# LTX-Rapidfire.net
KiCad netlist of a schematic drawn in EAGLE
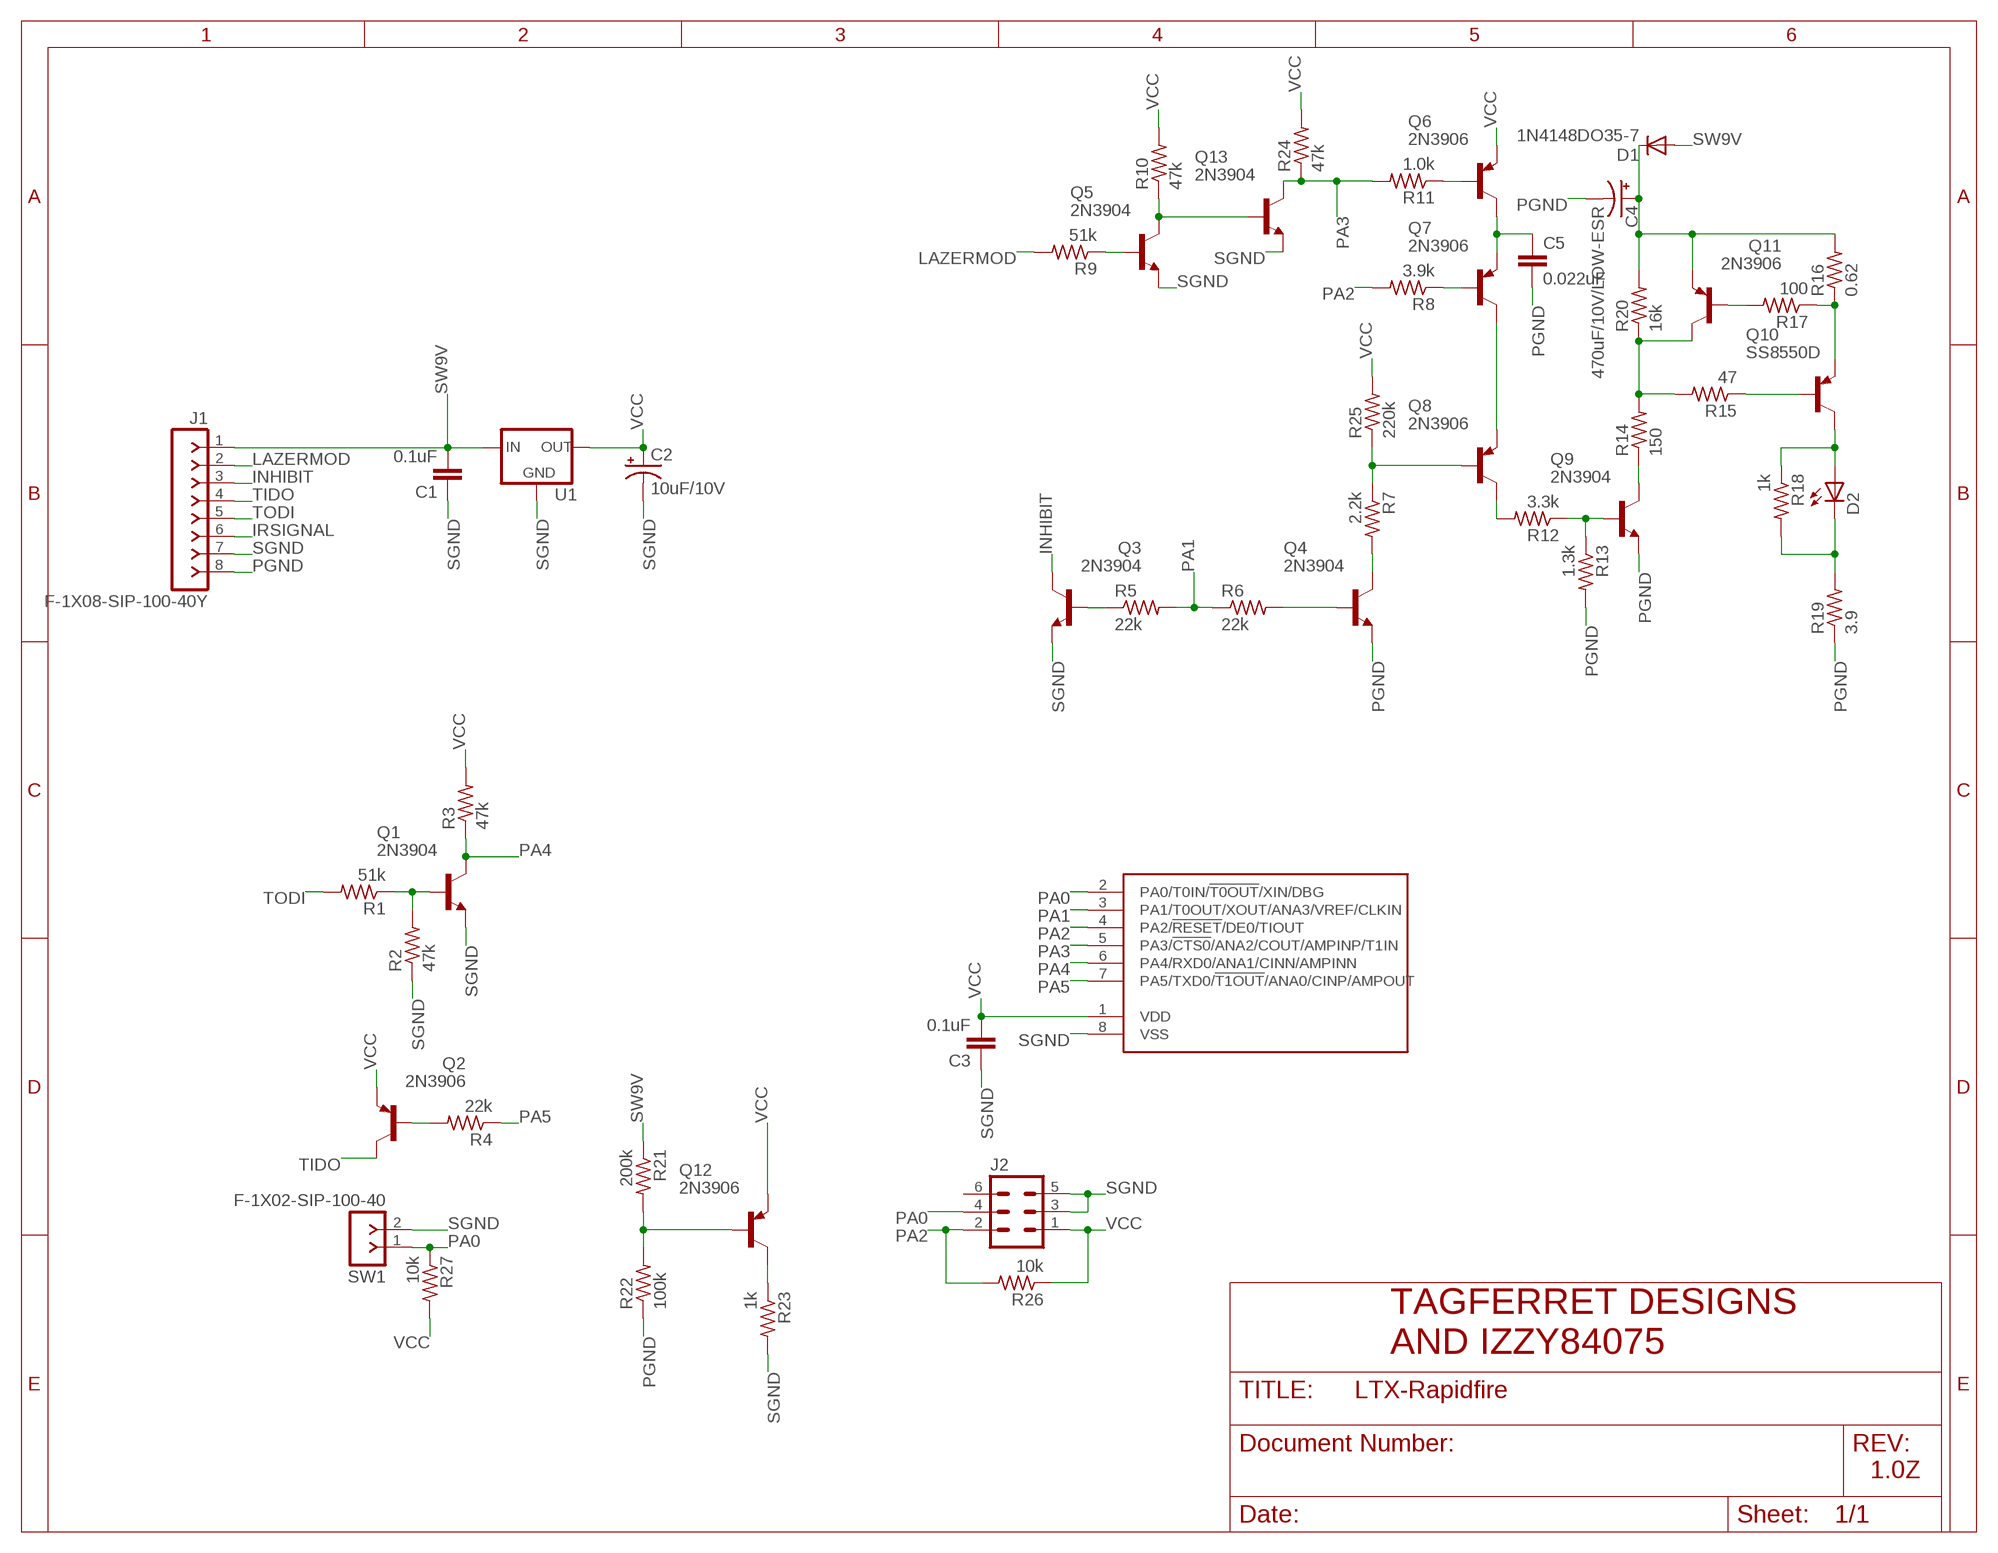
[diagram p0: schematic, sheet 1]

(export (version "E")
  (design (tool "Eeschema 10.0.6"))
  (components
    (comp (ref "C1")
      (value "0.1uF")
      (footprint "eagle-import:C025-025X050")
      (libsource (lib "eagle-import") (part "C-EU025-025X050"))
    )
    (comp (ref "C2")
      (value "10uF/10V")
      (footprint "eagle-import:E2-4")
      (libsource (lib "eagle-import") (part "CPOL-USE2-4"))
    )
    (comp (ref "C3")
      (value "0.1uF")
      (footprint "eagle-import:C025-025X050")
      (libsource (lib "eagle-import") (part "C-EU025-025X050"))
    )
    (comp (ref "C4")
      (value "470uF/10V/LOW-ESR")
      (footprint "eagle-import:E3,5-8")
      (libsource (lib "eagle-import") (part "CPOL-USE3.5-8"))
    )
    (comp (ref "C5")
      (value "0.022uF")
      (footprint "eagle-import:C025-025X050")
      (libsource (lib "eagle-import") (part "C-EU025-025X050"))
    )
    (comp (ref "D1")
      (value "1N4148DO35-7")
      (footprint "eagle-import:DO35-7")
      (libsource (lib "eagle-import") (part "1N4148DO35-7"))
    )
    (comp (ref "D2")
      (value "LED5MM")
      (footprint "eagle-import:LED5MM")
      (libsource (lib "eagle-import") (part "LED5MM"))
    )
    (comp (ref "J1")
      (value "F-1X08-SIP-100-40Y")
      (footprint "eagle-import:SIP-100-08-40Y")
      (libsource (lib "eagle-import") (part "F-1X08-SIP-100-40Y"))
    )
    (comp (ref "J2")
      (value "MA03-2")
      (footprint "eagle-import:MA03-2")
      (libsource (lib "eagle-import") (part "MA03-2"))
    )
    (comp (ref "Q1")
      (value "2N3904")
      (footprint "eagle-import:TO92")
      (libsource (lib "eagle-import") (part "2N3904"))
    )
    (comp (ref "Q2")
      (value "2N3906")
      (footprint "eagle-import:TO92")
      (libsource (lib "eagle-import") (part "2N3906"))
    )
    (comp (ref "Q3")
      (value "2N3904")
      (footprint "eagle-import:TO92")
      (libsource (lib "eagle-import") (part "2N3904"))
    )
    (comp (ref "Q4")
      (value "2N3904")
      (footprint "eagle-import:TO92")
      (libsource (lib "eagle-import") (part "2N3904"))
    )
    (comp (ref "Q5")
      (value "2N3904")
      (footprint "eagle-import:TO92")
      (libsource (lib "eagle-import") (part "2N3904"))
    )
    (comp (ref "Q6")
      (value "2N3906")
      (footprint "eagle-import:TO92")
      (libsource (lib "eagle-import") (part "2N3906"))
    )
    (comp (ref "Q7")
      (value "2N3906")
      (footprint "eagle-import:TO92")
      (libsource (lib "eagle-import") (part "2N3906"))
    )
    (comp (ref "Q8")
      (value "2N3906")
      (footprint "eagle-import:TO92")
      (libsource (lib "eagle-import") (part "2N3906"))
    )
    (comp (ref "Q9")
      (value "2N3904")
      (footprint "eagle-import:TO92")
      (libsource (lib "eagle-import") (part "2N3904"))
    )
    (comp (ref "Q10")
      (value "SS8550D")
      (footprint "eagle-import:TO92")
      (libsource (lib "eagle-import") (part "2N3906"))
    )
    (comp (ref "Q11")
      (value "2N3906")
      (footprint "eagle-import:TO92")
      (libsource (lib "eagle-import") (part "2N3906"))
    )
    (comp (ref "Q12")
      (value "2N3906")
      (footprint "eagle-import:TO92")
      (libsource (lib "eagle-import") (part "2N3906"))
    )
    (comp (ref "Q13")
      (value "2N3904")
      (footprint "eagle-import:TO92")
      (libsource (lib "eagle-import") (part "2N3904"))
    )
    (comp (ref "R1")
      (value "51k")
      (footprint "eagle-import:0204_7")
      (libsource (lib "eagle-import") (part "R-US_0204/7"))
    )
    (comp (ref "R2")
      (value "47k")
      (footprint "eagle-import:0204V")
      (libsource (lib "eagle-import") (part "R-US_0204/2V"))
    )
    (comp (ref "R3")
      (value "47k")
      (footprint "eagle-import:0204V")
      (libsource (lib "eagle-import") (part "R-US_0204/2V"))
    )
    (comp (ref "R4")
      (value "22k")
      (footprint "eagle-import:0204_7")
      (libsource (lib "eagle-import") (part "R-US_0204/7"))
    )
    (comp (ref "R5")
      (value "22k")
      (footprint "eagle-import:0204_7")
      (libsource (lib "eagle-import") (part "R-US_0204/7"))
    )
    (comp (ref "R6")
      (value "22k")
      (footprint "eagle-import:0204_7")
      (libsource (lib "eagle-import") (part "R-US_0204/7"))
    )
    (comp (ref "R7")
      (value "2.2k")
      (footprint "eagle-import:0204_7")
      (libsource (lib "eagle-import") (part "R-US_0204/7"))
    )
    (comp (ref "R8")
      (value "3.9k")
      (footprint "eagle-import:0204_7")
      (libsource (lib "eagle-import") (part "R-US_0204/7"))
    )
    (comp (ref "R9")
      (value "51k")
      (footprint "eagle-import:0204_7")
      (libsource (lib "eagle-import") (part "R-US_0204/7"))
    )
    (comp (ref "R10")
      (value "47k")
      (footprint "eagle-import:0204V")
      (libsource (lib "eagle-import") (part "R-US_0204/2V"))
    )
    (comp (ref "R11")
      (value "1.0k")
      (footprint "eagle-import:0204_7")
      (libsource (lib "eagle-import") (part "R-US_0204/7"))
    )
    (comp (ref "R12")
      (value "3.3k")
      (footprint "eagle-import:0204_7")
      (libsource (lib "eagle-import") (part "R-US_0204/7"))
    )
    (comp (ref "R13")
      (value "1.3k")
      (footprint "eagle-import:0204V")
      (libsource (lib "eagle-import") (part "R-US_0204/2V"))
    )
    (comp (ref "R14")
      (value "150")
      (footprint "eagle-import:0204_7")
      (libsource (lib "eagle-import") (part "R-US_0204/7"))
    )
    (comp (ref "R15")
      (value "47")
      (footprint "eagle-import:0204_7")
      (libsource (lib "eagle-import") (part "R-US_0204/7"))
    )
    (comp (ref "R16")
      (value "0.62")
      (footprint "eagle-import:0204_7")
      (libsource (lib "eagle-import") (part "R-US_0204/7"))
    )
    (comp (ref "R17")
      (value "100")
      (footprint "eagle-import:0204V")
      (libsource (lib "eagle-import") (part "R-US_0204/2V"))
    )
    (comp (ref "R18")
      (value "1k")
      (footprint "eagle-import:0204V")
      (libsource (lib "eagle-import") (part "R-US_0204/2V"))
    )
    (comp (ref "R19")
      (value "3.9")
      (footprint "eagle-import:0207_10")
      (libsource (lib "eagle-import") (part "R-US_0207/10"))
    )
    (comp (ref "R20")
      (value "16k")
      (footprint "eagle-import:0204V")
      (libsource (lib "eagle-import") (part "R-US_0204/2V"))
    )
    (comp (ref "R21")
      (value "200k")
      (footprint "eagle-import:0204_7")
      (libsource (lib "eagle-import") (part "R-US_0204/7"))
    )
    (comp (ref "R22")
      (value "100k")
      (footprint "eagle-import:0204V")
      (libsource (lib "eagle-import") (part "R-US_0204/2V"))
    )
    (comp (ref "R23")
      (value "1k")
      (footprint "eagle-import:0204_7")
      (libsource (lib "eagle-import") (part "R-US_0204/7"))
    )
    (comp (ref "R24")
      (value "47k")
      (footprint "eagle-import:0204V")
      (libsource (lib "eagle-import") (part "R-US_0204/2V"))
    )
    (comp (ref "R25")
      (value "220k")
      (footprint "eagle-import:0204V")
      (libsource (lib "eagle-import") (part "R-US_0204/2V"))
    )
    (comp (ref "R26")
      (value "10k")
      (footprint "eagle-import:0204V")
      (libsource (lib "eagle-import") (part "R-US_0204/2V"))
    )
    (comp (ref "R27")
      (value "10k")
      (footprint "eagle-import:0204V")
      (libsource (lib "eagle-import") (part "R-US_0204/2V"))
    )
    (comp (ref "SW1")
      (value "F-1X02-SIP-100-40")
      (footprint "eagle-import:SIP-100-02-40")
      (libsource (lib "eagle-import") (part "F-1X02-SIP-100-40"))
    )
    (comp (ref "U1")
      (value "78LXX")
      (footprint "eagle-import:78LXX")
      (libsource (lib "eagle-import") (part "78LXX"))
    )
    (comp (ref "U2")
      (value "Z8F082ADIL-8")
      (footprint "eagle-import:DIL8")
      (libsource (lib "eagle-import") (part "Z8F082ADIL-8"))
    )
  )
  (nets
    (net (code "1") (name "/INHIBIT") (class "Default")
      (node (ref "J1") (pin "3") (pinfunction "3_3") (pintype "passive"))
      (node (ref "Q3") (pin "1") (pinfunction "C_1") (pintype "passive"))
    )
    (net (code "2") (name "/IRSIGNAL") (class "Default")
      (node (ref "J1") (pin "6") (pinfunction "6_6") (pintype "passive"))
    )
    (net (code "3") (name "/LAZERMOD") (class "Default")
      (node (ref "J1") (pin "2") (pinfunction "2_2") (pintype "passive"))
      (node (ref "R9") (pin "2") (pinfunction "2_2") (pintype "passive"))
    )
    (net (code "4") (name "/PA0") (class "Default")
      (node (ref "J2") (pin "4") (pinfunction "4_4") (pintype "passive"))
      (node (ref "R27") (pin "1") (pinfunction "1_1") (pintype "passive"))
      (node (ref "SW1") (pin "1") (pinfunction "1_1") (pintype "passive"))
      (node (ref "U2") (pin "2") (pinfunction "PA0/T0IN/~{T0OUT}/XIN/DBG_2") (pintype "bidirectional"))
    )
    (net (code "5") (name "/PA1") (class "Default")
      (node (ref "R5") (pin "2") (pinfunction "2_2") (pintype "passive"))
      (node (ref "R6") (pin "1") (pinfunction "1_1") (pintype "passive"))
      (node (ref "U2") (pin "3") (pinfunction "PA1/T0OUT/XOUT/ANA3/VREF/CLKIN_3") (pintype "bidirectional"))
    )
    (net (code "6") (name "/PA2") (class "Default")
      (node (ref "J2") (pin "2") (pinfunction "2_2") (pintype "passive"))
      (node (ref "R26") (pin "2") (pinfunction "2_2") (pintype "passive"))
      (node (ref "R8") (pin "2") (pinfunction "2_2") (pintype "passive"))
      (node (ref "U2") (pin "4") (pinfunction "PA2/~{RESET}/DE0/TIOUT_4") (pintype "bidirectional"))
    )
    (net (code "7") (name "/PA3") (class "Default")
      (node (ref "Q13") (pin "1") (pinfunction "C_1") (pintype "passive"))
      (node (ref "R11") (pin "2") (pinfunction "2_2") (pintype "passive"))
      (node (ref "R24") (pin "1") (pinfunction "1_1") (pintype "passive"))
      (node (ref "U2") (pin "5") (pinfunction "PA3/~{CTS0}/ANA2/COUT/AMPINP/T1IN_5") (pintype "bidirectional"))
    )
    (net (code "8") (name "/PA4") (class "Default")
      (node (ref "Q1") (pin "1") (pinfunction "C_1") (pintype "passive"))
      (node (ref "R3") (pin "1") (pinfunction "1_1") (pintype "passive"))
      (node (ref "U2") (pin "6") (pinfunction "PA4/RXD0/ANA1/CINN/AMPINN_6") (pintype "bidirectional"))
    )
    (net (code "9") (name "/PA5") (class "Default")
      (node (ref "R4") (pin "1") (pinfunction "1_1") (pintype "passive"))
      (node (ref "U2") (pin "7") (pinfunction "PA5/TXD0/~{T1OUT}/ANA0/CINP/AMPOUT_7") (pintype "bidirectional"))
    )
    (net (code "10") (name "/PGND") (class "Default")
      (node (ref "C4") (pin "-") (pinfunction "-_-") (pintype "passive"))
      (node (ref "C5") (pin "2") (pinfunction "2_2") (pintype "passive"))
      (node (ref "J1") (pin "8") (pinfunction "8_8") (pintype "passive"))
      (node (ref "Q4") (pin "3") (pinfunction "E_3") (pintype "passive"))
      (node (ref "Q9") (pin "3") (pinfunction "E_3") (pintype "passive"))
      (node (ref "R13") (pin "2") (pinfunction "2_2") (pintype "passive"))
      (node (ref "R19") (pin "1") (pinfunction "1_1") (pintype "passive"))
      (node (ref "R22") (pin "1") (pinfunction "1_1") (pintype "passive"))
    )
    (net (code "11") (name "/SGND") (class "Default")
      (node (ref "C1") (pin "1") (pinfunction "1_1") (pintype "passive"))
      (node (ref "C2") (pin "-") (pinfunction "-_-") (pintype "passive"))
      (node (ref "C3") (pin "1") (pinfunction "1_1") (pintype "passive"))
      (node (ref "J1") (pin "7") (pinfunction "7_7") (pintype "passive"))
      (node (ref "J2") (pin "3") (pinfunction "3_3") (pintype "passive"))
      (node (ref "J2") (pin "5") (pinfunction "5_5") (pintype "passive"))
      (node (ref "Q1") (pin "3") (pinfunction "E_3") (pintype "passive"))
      (node (ref "Q13") (pin "3") (pinfunction "E_3") (pintype "passive"))
      (node (ref "Q3") (pin "3") (pinfunction "E_3") (pintype "passive"))
      (node (ref "Q5") (pin "3") (pinfunction "E_3") (pintype "passive"))
      (node (ref "R2") (pin "1") (pinfunction "1_1") (pintype "passive"))
      (node (ref "R23") (pin "2") (pinfunction "2_2") (pintype "passive"))
      (node (ref "SW1") (pin "2") (pinfunction "2_2") (pintype "passive"))
      (node (ref "U1") (pin "GND") (pinfunction "GND_GND") (pintype "input"))
      (node (ref "U2") (pin "8") (pinfunction "VSS_8") (pintype "bidirectional"))
    )
    (net (code "12") (name "/SW9V") (class "Default")
      (node (ref "C1") (pin "2") (pinfunction "2_2") (pintype "passive"))
      (node (ref "D1") (pin "A") (pinfunction "A_A") (pintype "passive"))
      (node (ref "J1") (pin "1") (pinfunction "1_1") (pintype "passive"))
      (node (ref "R21") (pin "1") (pinfunction "1_1") (pintype "passive"))
      (node (ref "U1") (pin "IN") (pinfunction "IN_IN") (pintype "input"))
    )
    (net (code "13") (name "/TIDO") (class "Default")
      (node (ref "J1") (pin "4") (pinfunction "4_4") (pintype "passive"))
      (node (ref "Q2") (pin "1") (pinfunction "C_1") (pintype "passive"))
    )
    (net (code "14") (name "/TODI") (class "Default")
      (node (ref "J1") (pin "5") (pinfunction "5_5") (pintype "passive"))
      (node (ref "R1") (pin "2") (pinfunction "2_2") (pintype "passive"))
    )
    (net (code "15") (name "/VCC") (class "Default")
      (node (ref "C2") (pin "+") (pinfunction "+_+") (pintype "passive"))
      (node (ref "C3") (pin "2") (pinfunction "2_2") (pintype "passive"))
      (node (ref "J2") (pin "1") (pinfunction "1_1") (pintype "passive"))
      (node (ref "Q12") (pin "3") (pinfunction "E_3") (pintype "passive"))
      (node (ref "Q2") (pin "3") (pinfunction "E_3") (pintype "passive"))
      (node (ref "Q6") (pin "3") (pinfunction "E_3") (pintype "passive"))
      (node (ref "R10") (pin "2") (pinfunction "2_2") (pintype "passive"))
      (node (ref "R24") (pin "2") (pinfunction "2_2") (pintype "passive"))
      (node (ref "R25") (pin "2") (pinfunction "2_2") (pintype "passive"))
      (node (ref "R26") (pin "1") (pinfunction "1_1") (pintype "passive"))
      (node (ref "R27") (pin "2") (pinfunction "2_2") (pintype "passive"))
      (node (ref "R3") (pin "2") (pinfunction "2_2") (pintype "passive"))
      (node (ref "U1") (pin "OUT") (pinfunction "OUT_OUT") (pintype "passive"))
      (node (ref "U2") (pin "1") (pinfunction "VDD_1") (pintype "bidirectional"))
    )
    (net (code "16") (name "Net-(D2-C)") (class "Default")
      (node (ref "D2") (pin "K") (pinfunction "C_K") (pintype "passive"))
      (node (ref "R18") (pin "2") (pinfunction "2_2") (pintype "passive"))
      (node (ref "R19") (pin "2") (pinfunction "2_2") (pintype "passive"))
    )
    (net (code "17") (name "Net-(Q1-B)") (class "Default")
      (node (ref "Q1") (pin "2") (pinfunction "B_2") (pintype "passive"))
      (node (ref "R1") (pin "1") (pinfunction "1_1") (pintype "passive"))
      (node (ref "R2") (pin "2") (pinfunction "2_2") (pintype "passive"))
    )
    (net (code "18") (name "Net-(Q2-B)") (class "Default")
      (node (ref "Q2") (pin "2") (pinfunction "B_2") (pintype "passive"))
      (node (ref "R4") (pin "2") (pinfunction "2_2") (pintype "passive"))
    )
    (net (code "19") (name "Net-(Q3-B)") (class "Default")
      (node (ref "Q3") (pin "2") (pinfunction "B_2") (pintype "passive"))
      (node (ref "R5") (pin "1") (pinfunction "1_1") (pintype "passive"))
    )
    (net (code "20") (name "Net-(Q4-B)") (class "Default")
      (node (ref "Q4") (pin "2") (pinfunction "B_2") (pintype "passive"))
      (node (ref "R6") (pin "2") (pinfunction "2_2") (pintype "passive"))
    )
    (net (code "21") (name "Net-(Q4-C)") (class "Default")
      (node (ref "Q4") (pin "1") (pinfunction "C_1") (pintype "passive"))
      (node (ref "R7") (pin "2") (pinfunction "2_2") (pintype "passive"))
    )
    (net (code "22") (name "Net-(Q5-B)") (class "Default")
      (node (ref "Q5") (pin "2") (pinfunction "B_2") (pintype "passive"))
      (node (ref "R9") (pin "1") (pinfunction "1_1") (pintype "passive"))
    )
    (net (code "23") (name "Net-(Q6-B)") (class "Default")
      (node (ref "Q6") (pin "2") (pinfunction "B_2") (pintype "passive"))
      (node (ref "R11") (pin "1") (pinfunction "1_1") (pintype "passive"))
    )
    (net (code "24") (name "Net-(Q6-C)") (class "Default")
      (node (ref "C5") (pin "1") (pinfunction "1_1") (pintype "passive"))
      (node (ref "Q6") (pin "1") (pinfunction "C_1") (pintype "passive"))
      (node (ref "Q7") (pin "3") (pinfunction "E_3") (pintype "passive"))
    )
    (net (code "25") (name "Net-(Q7-B)") (class "Default")
      (node (ref "Q7") (pin "2") (pinfunction "B_2") (pintype "passive"))
      (node (ref "R8") (pin "1") (pinfunction "1_1") (pintype "passive"))
    )
    (net (code "26") (name "Net-(Q7-C)") (class "Default")
      (node (ref "Q7") (pin "1") (pinfunction "C_1") (pintype "passive"))
      (node (ref "Q8") (pin "3") (pinfunction "E_3") (pintype "passive"))
    )
    (net (code "27") (name "Net-(Q8-B)") (class "Default")
      (node (ref "Q8") (pin "2") (pinfunction "B_2") (pintype "passive"))
      (node (ref "R25") (pin "1") (pinfunction "1_1") (pintype "passive"))
      (node (ref "R7") (pin "1") (pinfunction "1_1") (pintype "passive"))
    )
    (net (code "28") (name "Net-(Q8-C)") (class "Default")
      (node (ref "Q8") (pin "1") (pinfunction "C_1") (pintype "passive"))
      (node (ref "R12") (pin "2") (pinfunction "2_2") (pintype "passive"))
    )
    (net (code "29") (name "Net-(Q9-B)") (class "Default")
      (node (ref "Q9") (pin "2") (pinfunction "B_2") (pintype "passive"))
      (node (ref "R12") (pin "1") (pinfunction "1_1") (pintype "passive"))
      (node (ref "R13") (pin "1") (pinfunction "1_1") (pintype "passive"))
    )
    (net (code "30") (name "Net-(Q9-C)") (class "Default")
      (node (ref "Q9") (pin "1") (pinfunction "C_1") (pintype "passive"))
      (node (ref "R14") (pin "1") (pinfunction "1_1") (pintype "passive"))
    )
    (net (code "31") (name "Net-(Q10-B)") (class "Default")
      (node (ref "Q10") (pin "2") (pinfunction "B_2") (pintype "passive"))
      (node (ref "R15") (pin "1") (pinfunction "1_1") (pintype "passive"))
    )
    (net (code "32") (name "Net-(Q10-C)") (class "Default")
      (node (ref "D2") (pin "A") (pinfunction "A_A") (pintype "passive"))
      (node (ref "Q10") (pin "1") (pinfunction "C_1") (pintype "passive"))
      (node (ref "R18") (pin "1") (pinfunction "1_1") (pintype "passive"))
    )
    (net (code "33") (name "Net-(Q10-E)") (class "Default")
      (node (ref "Q10") (pin "3") (pinfunction "E_3") (pintype "passive"))
      (node (ref "R16") (pin "1") (pinfunction "1_1") (pintype "passive"))
      (node (ref "R17") (pin "1") (pinfunction "1_1") (pintype "passive"))
    )
    (net (code "34") (name "Net-(Q11-B)") (class "Default")
      (node (ref "Q11") (pin "2") (pinfunction "B_2") (pintype "passive"))
      (node (ref "R17") (pin "2") (pinfunction "2_2") (pintype "passive"))
    )
    (net (code "35") (name "Net-(Q11-C)") (class "Default")
      (node (ref "Q11") (pin "1") (pinfunction "C_1") (pintype "passive"))
      (node (ref "R14") (pin "2") (pinfunction "2_2") (pintype "passive"))
      (node (ref "R15") (pin "2") (pinfunction "2_2") (pintype "passive"))
      (node (ref "R20") (pin "1") (pinfunction "1_1") (pintype "passive"))
    )
    (net (code "36") (name "Net-(Q11-E)") (class "Default")
      (node (ref "C4") (pin "+") (pinfunction "+_+") (pintype "passive"))
      (node (ref "D1") (pin "C") (pinfunction "C_C") (pintype "passive"))
      (node (ref "Q11") (pin "3") (pinfunction "E_3") (pintype "passive"))
      (node (ref "R16") (pin "2") (pinfunction "2_2") (pintype "passive"))
      (node (ref "R20") (pin "2") (pinfunction "2_2") (pintype "passive"))
    )
    (net (code "37") (name "Net-(Q12-B)") (class "Default")
      (node (ref "Q12") (pin "2") (pinfunction "B_2") (pintype "passive"))
      (node (ref "R21") (pin "2") (pinfunction "2_2") (pintype "passive"))
      (node (ref "R22") (pin "2") (pinfunction "2_2") (pintype "passive"))
    )
    (net (code "38") (name "Net-(Q12-C)") (class "Default")
      (node (ref "Q12") (pin "1") (pinfunction "C_1") (pintype "passive"))
      (node (ref "R23") (pin "1") (pinfunction "1_1") (pintype "passive"))
    )
    (net (code "39") (name "Net-(Q13-B)") (class "Default")
      (node (ref "Q13") (pin "2") (pinfunction "B_2") (pintype "passive"))
      (node (ref "Q5") (pin "1") (pinfunction "C_1") (pintype "passive"))
      (node (ref "R10") (pin "1") (pinfunction "1_1") (pintype "passive"))
    )
    (net (code "40") (name "unconnected-(J2-Pad6)") (class "Default")
      (node (ref "J2") (pin "6") (pinfunction "6_6") (pintype "passive"))
    )
  )
)
